# 04_-BUTTON.net
KiCad netlist of a schematic drawn in Altium Designer
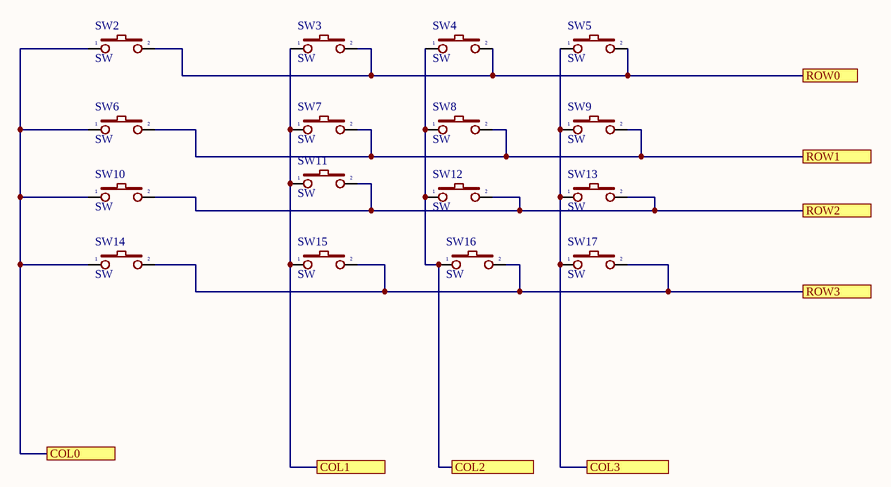
[diagram p0: [04]-BUTTON.SchDoc]

(export (version "E")
  (design (tool "Eeschema 10.0.6"))
  (components
    (comp (ref "SW2")
      (value "SW")
      (footprint "SW2")
      (description "Switch button 2 pin")
      (libsource (lib "My Library") (part "SW2"))
    )
    (comp (ref "SW3")
      (value "SW")
      (footprint "SW2")
      (description "Switch button 2 pin")
      (libsource (lib "My Library") (part "SW2"))
    )
    (comp (ref "SW4")
      (value "SW")
      (footprint "SW2")
      (description "Switch button 2 pin")
      (libsource (lib "My Library") (part "SW2"))
    )
    (comp (ref "SW5")
      (value "SW")
      (footprint "SW2")
      (description "Switch button 2 pin")
      (libsource (lib "My Library") (part "SW2"))
    )
    (comp (ref "SW6")
      (value "SW")
      (footprint "SW2")
      (description "Switch button 2 pin")
      (libsource (lib "My Library") (part "SW2"))
    )
    (comp (ref "SW7")
      (value "SW")
      (footprint "SW2")
      (description "Switch button 2 pin")
      (libsource (lib "My Library") (part "SW2"))
    )
    (comp (ref "SW8")
      (value "SW")
      (footprint "SW2")
      (description "Switch button 2 pin")
      (libsource (lib "My Library") (part "SW2"))
    )
    (comp (ref "SW9")
      (value "SW")
      (footprint "SW2")
      (description "Switch button 2 pin")
      (libsource (lib "My Library") (part "SW2"))
    )
    (comp (ref "SW10")
      (value "SW")
      (footprint "SW2")
      (description "Switch button 2 pin")
      (libsource (lib "My Library") (part "SW2"))
    )
    (comp (ref "SW11")
      (value "SW")
      (footprint "SW2")
      (description "Switch button 2 pin")
      (libsource (lib "My Library") (part "SW2"))
    )
    (comp (ref "SW12")
      (value "SW")
      (footprint "SW2")
      (description "Switch button 2 pin")
      (libsource (lib "My Library") (part "SW2"))
    )
    (comp (ref "SW13")
      (value "SW")
      (footprint "SW2")
      (description "Switch button 2 pin")
      (libsource (lib "My Library") (part "SW2"))
    )
    (comp (ref "SW14")
      (value "SW")
      (footprint "SW2")
      (description "Switch button 2 pin")
      (libsource (lib "My Library") (part "SW2"))
    )
    (comp (ref "SW15")
      (value "SW")
      (footprint "SW2")
      (description "Switch button 2 pin")
      (libsource (lib "My Library") (part "SW2"))
    )
    (comp (ref "SW16")
      (value "SW")
      (footprint "SW2")
      (description "Switch button 2 pin")
      (libsource (lib "My Library") (part "SW2"))
    )
    (comp (ref "SW17")
      (value "SW")
      (footprint "SW2")
      (description "Switch button 2 pin")
      (libsource (lib "My Library") (part "SW2"))
    )
  )
  (nets
    (net (code "1") (name "/COL0") (class "Default")
      (node (ref "SW10") (pin "1") (pinfunction "1_1") (pintype "passive"))
      (node (ref "SW14") (pin "1") (pinfunction "1_1") (pintype "passive"))
      (node (ref "SW2") (pin "1") (pinfunction "1_1") (pintype "passive"))
      (node (ref "SW6") (pin "1") (pinfunction "1_1") (pintype "passive"))
    )
    (net (code "2") (name "/COL1") (class "Default")
      (node (ref "SW11") (pin "1") (pinfunction "1_1") (pintype "passive"))
      (node (ref "SW15") (pin "1") (pinfunction "1_1") (pintype "passive"))
      (node (ref "SW3") (pin "1") (pinfunction "1_1") (pintype "passive"))
      (node (ref "SW7") (pin "1") (pinfunction "1_1") (pintype "passive"))
    )
    (net (code "3") (name "/COL2") (class "Default")
      (node (ref "SW12") (pin "1") (pinfunction "1_1") (pintype "passive"))
      (node (ref "SW16") (pin "1") (pinfunction "1_1") (pintype "passive"))
      (node (ref "SW4") (pin "1") (pinfunction "1_1") (pintype "passive"))
      (node (ref "SW8") (pin "1") (pinfunction "1_1") (pintype "passive"))
    )
    (net (code "4") (name "/COL3") (class "Default")
      (node (ref "SW13") (pin "1") (pinfunction "1_1") (pintype "passive"))
      (node (ref "SW17") (pin "1") (pinfunction "1_1") (pintype "passive"))
      (node (ref "SW5") (pin "1") (pinfunction "1_1") (pintype "passive"))
      (node (ref "SW9") (pin "1") (pinfunction "1_1") (pintype "passive"))
    )
    (net (code "5") (name "/ROW0") (class "Default")
      (node (ref "SW2") (pin "2") (pinfunction "2_2") (pintype "passive"))
      (node (ref "SW3") (pin "2") (pinfunction "2_2") (pintype "passive"))
      (node (ref "SW4") (pin "2") (pinfunction "2_2") (pintype "passive"))
      (node (ref "SW5") (pin "2") (pinfunction "2_2") (pintype "passive"))
    )
    (net (code "6") (name "/ROW1") (class "Default")
      (node (ref "SW6") (pin "2") (pinfunction "2_2") (pintype "passive"))
      (node (ref "SW7") (pin "2") (pinfunction "2_2") (pintype "passive"))
      (node (ref "SW8") (pin "2") (pinfunction "2_2") (pintype "passive"))
      (node (ref "SW9") (pin "2") (pinfunction "2_2") (pintype "passive"))
    )
    (net (code "7") (name "/ROW2") (class "Default")
      (node (ref "SW10") (pin "2") (pinfunction "2_2") (pintype "passive"))
      (node (ref "SW11") (pin "2") (pinfunction "2_2") (pintype "passive"))
      (node (ref "SW12") (pin "2") (pinfunction "2_2") (pintype "passive"))
      (node (ref "SW13") (pin "2") (pinfunction "2_2") (pintype "passive"))
    )
    (net (code "8") (name "/ROW3") (class "Default")
      (node (ref "SW14") (pin "2") (pinfunction "2_2") (pintype "passive"))
      (node (ref "SW15") (pin "2") (pinfunction "2_2") (pintype "passive"))
      (node (ref "SW16") (pin "2") (pinfunction "2_2") (pintype "passive"))
      (node (ref "SW17") (pin "2") (pinfunction "2_2") (pintype "passive"))
    )
  )
)
